# Light_Shield_Test.net
KiCad netlist of a schematic drawn in EAGLE
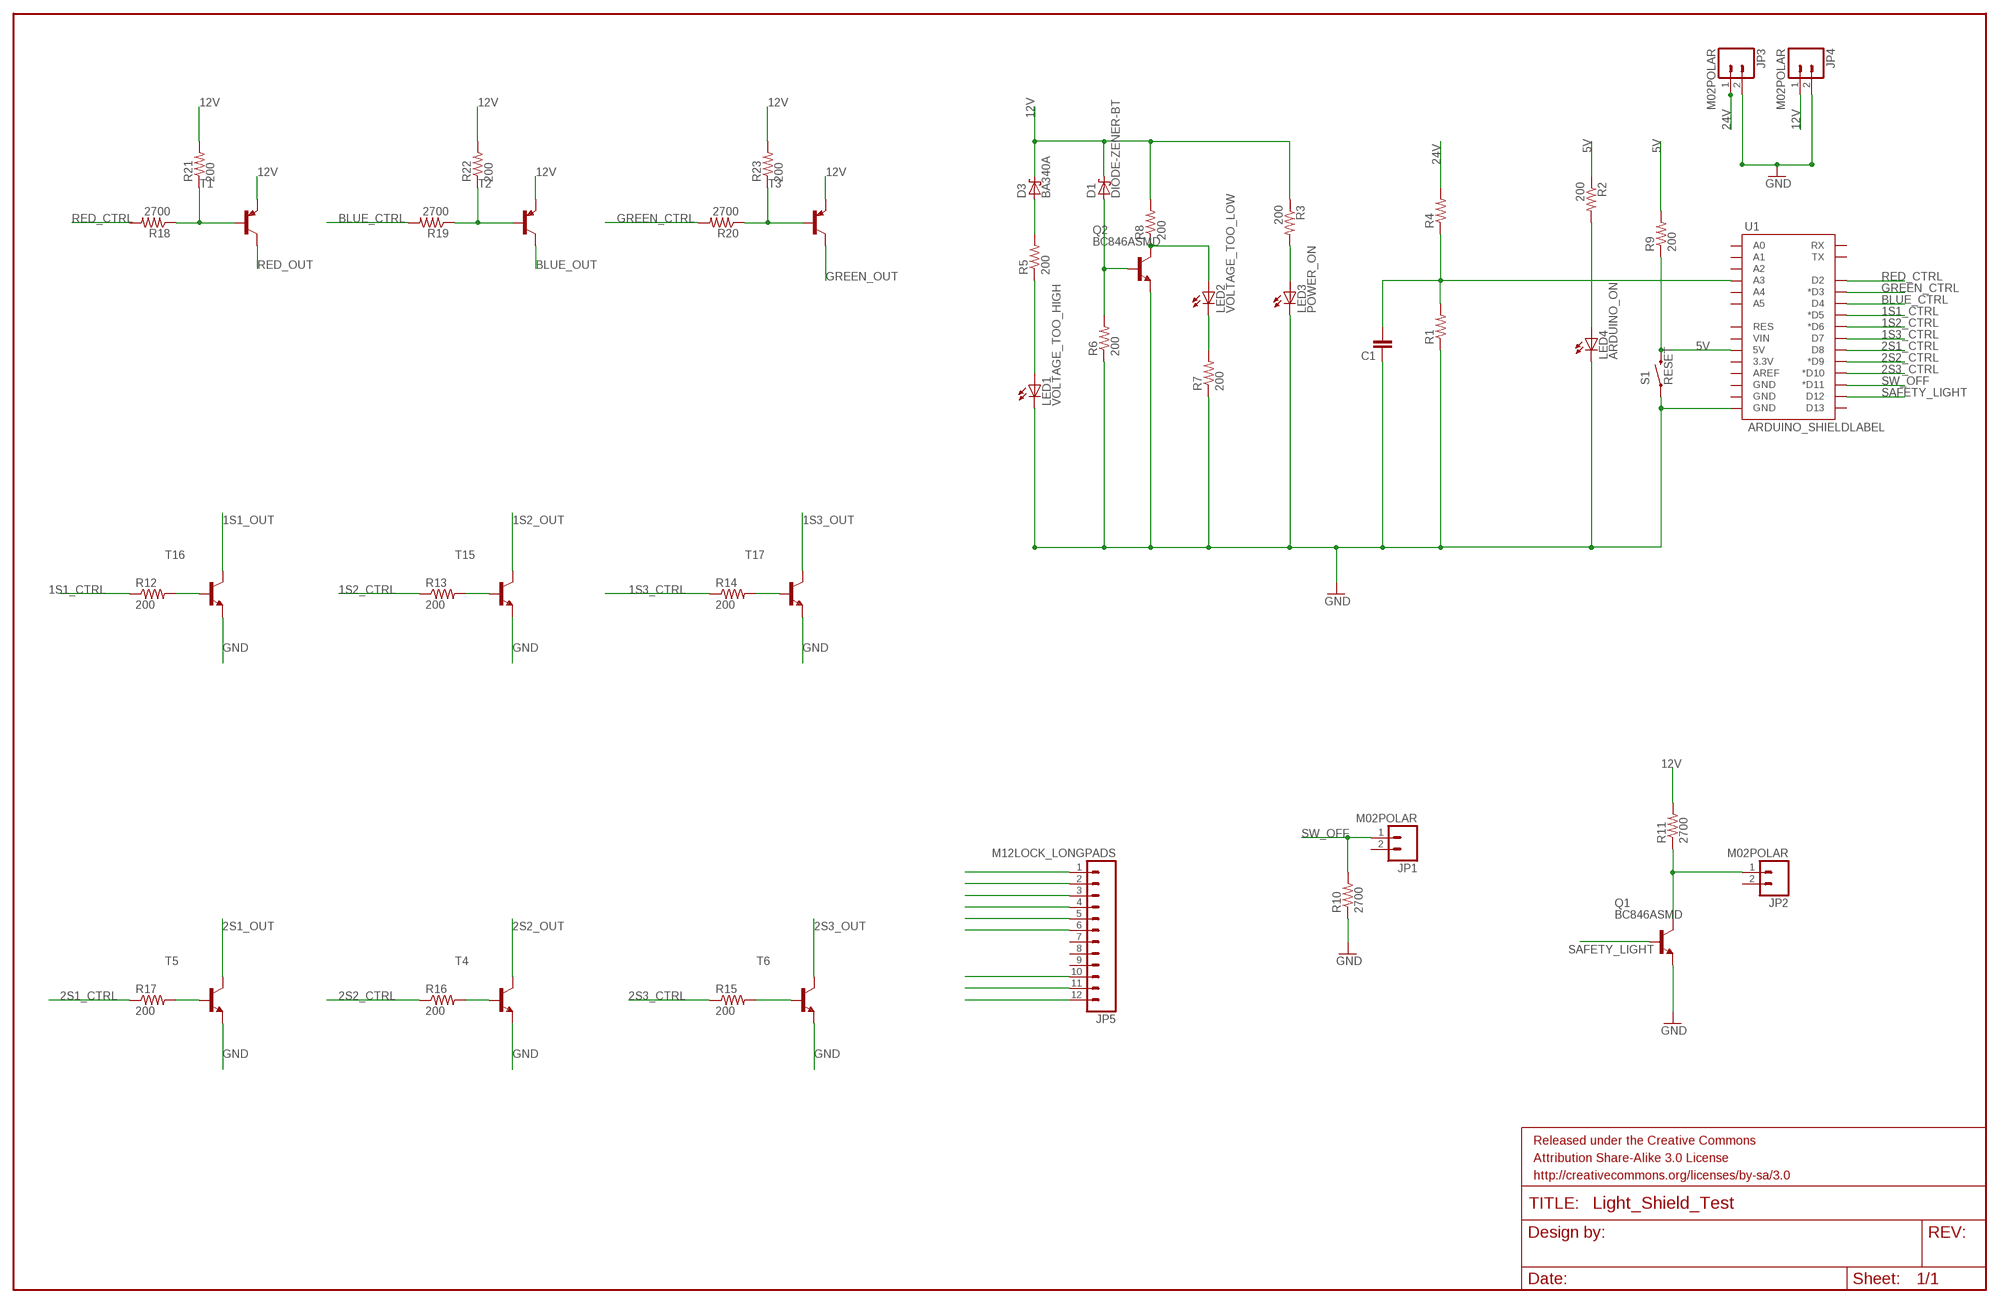
[diagram p0: schematic, sheet 1]

(export (version "E")
  (design (tool "Eeschema 10.0.6"))
  (components
    (comp (ref "C1")
      (value "CAP0402-CAP")
      (footprint "eagle-import:0402-CAP")
      (libsource (lib "eagle-import") (part "CAP0402-CAP"))
    )
    (comp (ref "D1")
      (value "DIODE-ZENER-BT")
      (footprint "eagle-import:SOD123FL")
      (libsource (lib "eagle-import") (part "SMF5.0AT1"))
    )
    (comp (ref "D3")
      (value "BA340A")
      (footprint "eagle-import:SOD123FL")
      (libsource (lib "eagle-import") (part "SMF5.0AT1"))
    )
    (comp (ref "FRAME1")
      (value "FRAME-LEDGER")
      (footprint "eagle-import:CREATIVE_COMMONS")
      (libsource (lib "eagle-import") (part "FRAME-LEDGER"))
    )
    (comp (ref "JP1")
      (value "M02POLAR")
      (footprint "eagle-import:MOLEX-1X2")
      (libsource (lib "eagle-import") (part "M02POLAR"))
    )
    (comp (ref "JP2")
      (value "M02POLAR")
      (footprint "eagle-import:MOLEX-1X2")
      (libsource (lib "eagle-import") (part "M02POLAR"))
    )
    (comp (ref "JP3")
      (value "M02POLAR")
      (footprint "eagle-import:MOLEX-1X2")
      (libsource (lib "eagle-import") (part "M02POLAR"))
    )
    (comp (ref "JP4")
      (value "M02POLAR")
      (footprint "eagle-import:MOLEX-1X2")
      (libsource (lib "eagle-import") (part "M02POLAR"))
    )
    (comp (ref "JP5")
      (value "M12LOCK_LONGPADS")
      (footprint "eagle-import:1X12_LOCK_LONGPADS")
      (libsource (lib "eagle-import") (part "M12LOCK_LONGPADS"))
    )
    (comp (ref "LED1")
      (value "VOLTAGE_TOO_HIGH")
      (footprint "eagle-import:SML0603")
      (libsource (lib "eagle-import") (part "LEDSML0603"))
    )
    (comp (ref "LED2")
      (value "VOLTAGE_TOO_LOW")
      (footprint "eagle-import:SML0603")
      (libsource (lib "eagle-import") (part "LEDSML0603"))
    )
    (comp (ref "LED3")
      (value "POWER_ON")
      (footprint "eagle-import:SML0603")
      (libsource (lib "eagle-import") (part "LEDSML0603"))
    )
    (comp (ref "LED4")
      (value "ARDUINO_ON")
      (footprint "eagle-import:SML0603")
      (libsource (lib "eagle-import") (part "LEDSML0603"))
    )
    (comp (ref "Q1")
      (value "BC846ASMD")
      (footprint "eagle-import:SOT23")
      (libsource (lib "eagle-import") (part "BC846SMDA"))
    )
    (comp (ref "Q2")
      (value "BC846ASMD")
      (footprint "eagle-import:SOT23")
      (libsource (lib "eagle-import") (part "BC846SMDA"))
    )
    (comp (ref "R1")
      (value "RESISTOR0402-RES")
      (footprint "eagle-import:0402-RES")
      (libsource (lib "eagle-import") (part "RESISTOR0402-RES"))
    )
    (comp (ref "R2")
      (value "200")
      (footprint "eagle-import:0603-RES")
      (libsource (lib "eagle-import") (part "RESISTOR0603"))
    )
    (comp (ref "R3")
      (value "200")
      (footprint "eagle-import:0603-RES")
      (libsource (lib "eagle-import") (part "RESISTOR0603"))
    )
    (comp (ref "R4")
      (value "RESISTOR0603")
      (footprint "eagle-import:0603-RES")
      (libsource (lib "eagle-import") (part "RESISTOR0603"))
    )
    (comp (ref "R5")
      (value "200")
      (footprint "eagle-import:0603-RES")
      (libsource (lib "eagle-import") (part "RESISTOR0603"))
    )
    (comp (ref "R6")
      (value "200")
      (footprint "eagle-import:0603-RES")
      (libsource (lib "eagle-import") (part "RESISTOR0603"))
    )
    (comp (ref "R7")
      (value "200")
      (footprint "eagle-import:0603-RES")
      (libsource (lib "eagle-import") (part "SparkFun-Resistors_RESISTOR0603-RES"))
    )
    (comp (ref "R8")
      (value "200")
      (footprint "eagle-import:0603-RES")
      (libsource (lib "eagle-import") (part "SparkFun-Resistors_RESISTOR0603-RES"))
    )
    (comp (ref "R9")
      (value "200")
      (footprint "eagle-import:0603-RES")
      (libsource (lib "eagle-import") (part "RESISTOR0603"))
    )
    (comp (ref "R10")
      (value "2700")
      (footprint "eagle-import:0603-RES")
      (libsource (lib "eagle-import") (part "RESISTOR0603"))
    )
    (comp (ref "R11")
      (value "2700")
      (footprint "eagle-import:0603-RES")
      (libsource (lib "eagle-import") (part "RESISTOR0603"))
    )
    (comp (ref "R12")
      (value "200")
      (footprint "eagle-import:0603-RES")
      (libsource (lib "eagle-import") (part "RESISTOR0603"))
    )
    (comp (ref "R13")
      (value "200")
      (footprint "eagle-import:0603-RES")
      (libsource (lib "eagle-import") (part "RESISTOR0603"))
    )
    (comp (ref "R14")
      (value "200")
      (footprint "eagle-import:0603-RES")
      (libsource (lib "eagle-import") (part "RESISTOR0603"))
    )
    (comp (ref "R15")
      (value "200")
      (footprint "eagle-import:0603-RES")
      (libsource (lib "eagle-import") (part "RESISTOR0603"))
    )
    (comp (ref "R16")
      (value "200")
      (footprint "eagle-import:0603-RES")
      (libsource (lib "eagle-import") (part "RESISTOR0603"))
    )
    (comp (ref "R17")
      (value "200")
      (footprint "eagle-import:0603-RES")
      (libsource (lib "eagle-import") (part "RESISTOR0603"))
    )
    (comp (ref "R18")
      (value "2700")
      (footprint "eagle-import:0603-RES")
      (libsource (lib "eagle-import") (part "RESISTOR0603"))
    )
    (comp (ref "R19")
      (value "2700")
      (footprint "eagle-import:0603-RES")
      (libsource (lib "eagle-import") (part "RESISTOR0603"))
    )
    (comp (ref "R20")
      (value "2700")
      (footprint "eagle-import:0603-RES")
      (libsource (lib "eagle-import") (part "RESISTOR0603"))
    )
    (comp (ref "R21")
      (value "200")
      (footprint "eagle-import:0603-RES")
      (libsource (lib "eagle-import") (part "RESISTOR0603"))
    )
    (comp (ref "R22")
      (value "200")
      (footprint "eagle-import:0603-RES")
      (libsource (lib "eagle-import") (part "RESISTOR0603"))
    )
    (comp (ref "R23")
      (value "200")
      (footprint "eagle-import:0603-RES")
      (libsource (lib "eagle-import") (part "RESISTOR0603"))
    )
    (comp (ref "S1")
      (value "RESET")
      (footprint "eagle-import:TACTILE-PTH")
      (libsource (lib "eagle-import") (part "SWITCH-MOMENTARY-2PTH"))
    )
    (comp (ref "T1")
      (value "-PNP-TO220V")
      (footprint "eagle-import:TO220V")
      (libsource (lib "eagle-import") (part "-PNP-TO220V"))
    )
    (comp (ref "T2")
      (value "-PNP-TO220V")
      (footprint "eagle-import:TO220V")
      (libsource (lib "eagle-import") (part "-PNP-TO220V"))
    )
    (comp (ref "T3")
      (value "-PNP-TO220V")
      (footprint "eagle-import:TO220V")
      (libsource (lib "eagle-import") (part "-PNP-TO220V"))
    )
    (comp (ref "T4")
      (value "-NPN-TO220V")
      (footprint "eagle-import:TO220V")
      (libsource (lib "eagle-import") (part "-NPN-TO220V"))
    )
    (comp (ref "T5")
      (value "-NPN-TO220V")
      (footprint "eagle-import:TO220V")
      (libsource (lib "eagle-import") (part "-NPN-TO220V"))
    )
    (comp (ref "T6")
      (value "-NPN-TO220V")
      (footprint "eagle-import:TO220V")
      (libsource (lib "eagle-import") (part "-NPN-TO220V"))
    )
    (comp (ref "T15")
      (value "-NPN-TO220V")
      (footprint "eagle-import:TO220V")
      (libsource (lib "eagle-import") (part "-NPN-TO220V"))
    )
    (comp (ref "T16")
      (value "-NPN-TO220V")
      (footprint "eagle-import:TO220V")
      (libsource (lib "eagle-import") (part "-NPN-TO220V"))
    )
    (comp (ref "T17")
      (value "-NPN-TO220V")
      (footprint "eagle-import:TO220V")
      (libsource (lib "eagle-import") (part "-NPN-TO220V"))
    )
    (comp (ref "U1")
      (value "ARDUINO_SHIELDLABEL")
      (footprint "eagle-import:DUEMILANOVE_SHIELD")
      (libsource (lib "eagle-import") (part "ARDUINO_SHIELDLABEL"))
    )
  )
  (nets
    (net (code "1") (name "/1S1_CTRL") (class "Default")
      (node (ref "R12") (pin "1") (pinfunction "1_1") (pintype "passive"))
      (node (ref "U1") (pin "D5") (pinfunction "*D5_D5") (pintype "bidirectional"))
    )
    (net (code "2") (name "/1S1_OUT") (class "Default")
      (node (ref "JP5") (pin "4") (pinfunction "4_4") (pintype "passive"))
      (node (ref "T16") (pin "2") (pinfunction "C_2") (pintype "passive"))
    )
    (net (code "3") (name "/1S2_CTRL") (class "Default")
      (node (ref "R13") (pin "1") (pinfunction "1_1") (pintype "passive"))
      (node (ref "U1") (pin "D6") (pinfunction "*D6_D6") (pintype "bidirectional"))
    )
    (net (code "4") (name "/1S2_OUT") (class "Default")
      (node (ref "JP5") (pin "5") (pinfunction "5_5") (pintype "passive"))
      (node (ref "T15") (pin "2") (pinfunction "C_2") (pintype "passive"))
    )
    (net (code "5") (name "/1S3_CTRL") (class "Default")
      (node (ref "R14") (pin "1") (pinfunction "1_1") (pintype "passive"))
      (node (ref "U1") (pin "D7") (pinfunction "D7_D7") (pintype "bidirectional"))
    )
    (net (code "6") (name "/1S3_OUT") (class "Default")
      (node (ref "JP5") (pin "6") (pinfunction "6_6") (pintype "passive"))
      (node (ref "T17") (pin "2") (pinfunction "C_2") (pintype "passive"))
    )
    (net (code "7") (name "/2S1_CTRL") (class "Default")
      (node (ref "R17") (pin "1") (pinfunction "1_1") (pintype "passive"))
      (node (ref "U1") (pin "D8") (pinfunction "D8_D8") (pintype "bidirectional"))
    )
    (net (code "8") (name "/2S1_OUT") (class "Default")
      (node (ref "JP5") (pin "10") (pinfunction "10_10") (pintype "passive"))
      (node (ref "T5") (pin "2") (pinfunction "C_2") (pintype "passive"))
    )
    (net (code "9") (name "/2S2_CTRL") (class "Default")
      (node (ref "R16") (pin "1") (pinfunction "1_1") (pintype "passive"))
      (node (ref "U1") (pin "D9") (pinfunction "*D9_D9") (pintype "bidirectional"))
    )
    (net (code "10") (name "/2S2_OUT") (class "Default")
      (node (ref "JP5") (pin "11") (pinfunction "11_11") (pintype "passive"))
      (node (ref "T4") (pin "2") (pinfunction "C_2") (pintype "passive"))
    )
    (net (code "11") (name "/2S3_CTRL") (class "Default")
      (node (ref "R15") (pin "1") (pinfunction "1_1") (pintype "passive"))
      (node (ref "U1") (pin "D10") (pinfunction "*D10_D10") (pintype "bidirectional"))
    )
    (net (code "12") (name "/2S3_OUT") (class "Default")
      (node (ref "JP5") (pin "12") (pinfunction "12_12") (pintype "passive"))
      (node (ref "T6") (pin "2") (pinfunction "C_2") (pintype "passive"))
    )
    (net (code "13") (name "/5V") (class "Default")
      (node (ref "R2") (pin "1") (pinfunction "1_1") (pintype "passive"))
      (node (ref "R9") (pin "1") (pinfunction "1_1") (pintype "passive"))
      (node (ref "R9") (pin "2") (pinfunction "2_2") (pintype "passive"))
      (node (ref "S1") (pin "3") (pinfunction "2_3") (pintype "passive"))
      (node (ref "U1") (pin "5V") (pinfunction "5V_5V") (pintype "bidirectional"))
    )
    (net (code "14") (name "/12V") (class "Default")
      (node (ref "D1") (pin "C") (pinfunction "C_C") (pintype "passive"))
      (node (ref "D3") (pin "C") (pinfunction "C_C") (pintype "passive"))
      (node (ref "JP4") (pin "1") (pinfunction "1_1") (pintype "passive"))
      (node (ref "R11") (pin "2") (pinfunction "2_2") (pintype "passive"))
      (node (ref "R21") (pin "2") (pinfunction "2_2") (pintype "passive"))
      (node (ref "R22") (pin "2") (pinfunction "2_2") (pintype "passive"))
      (node (ref "R23") (pin "2") (pinfunction "2_2") (pintype "passive"))
      (node (ref "R3") (pin "1") (pinfunction "1_1") (pintype "passive"))
      (node (ref "R8") (pin "2") (pinfunction "2_2") (pintype "passive"))
      (node (ref "T1") (pin "3") (pinfunction "E_3") (pintype "passive"))
      (node (ref "T2") (pin "3") (pinfunction "E_3") (pintype "passive"))
      (node (ref "T3") (pin "3") (pinfunction "E_3") (pintype "passive"))
    )
    (net (code "15") (name "/24V") (class "Default")
      (node (ref "JP3") (pin "1") (pinfunction "1_1") (pintype "passive"))
      (node (ref "R4") (pin "2") (pinfunction "2_2") (pintype "passive"))
    )
    (net (code "16") (name "/BLUE_CTRL") (class "Default")
      (node (ref "R19") (pin "2") (pinfunction "2_2") (pintype "passive"))
      (node (ref "U1") (pin "D4") (pinfunction "D4_D4") (pintype "bidirectional"))
    )
    (net (code "17") (name "/BLUE_OUT") (class "Default")
      (node (ref "JP5") (pin "1") (pinfunction "1_1") (pintype "passive"))
      (node (ref "T2") (pin "2") (pinfunction "C_2") (pintype "passive"))
    )
    (net (code "18") (name "/GREEN_CTRL") (class "Default")
      (node (ref "R20") (pin "2") (pinfunction "2_2") (pintype "passive"))
      (node (ref "U1") (pin "D3") (pinfunction "*D3_D3") (pintype "bidirectional"))
    )
    (net (code "19") (name "/GREEN_OUT") (class "Default")
      (node (ref "JP5") (pin "2") (pinfunction "2_2") (pintype "passive"))
      (node (ref "T3") (pin "2") (pinfunction "C_2") (pintype "passive"))
    )
    (net (code "20") (name "/RED_CTRL") (class "Default")
      (node (ref "R18") (pin "2") (pinfunction "2_2") (pintype "passive"))
      (node (ref "U1") (pin "D2") (pinfunction "D2_D2") (pintype "bidirectional"))
    )
    (net (code "21") (name "/RED_OUT") (class "Default")
      (node (ref "JP5") (pin "3") (pinfunction "3_3") (pintype "passive"))
      (node (ref "T1") (pin "2") (pinfunction "C_2") (pintype "passive"))
    )
    (net (code "22") (name "/SAFETY_LIGHT") (class "Default")
      (node (ref "Q1") (pin "1") (pinfunction "B_1") (pintype "passive"))
      (node (ref "U1") (pin "D12") (pinfunction "D12_D12") (pintype "bidirectional"))
    )
    (net (code "23") (name "/SW_OFF") (class "Default")
      (node (ref "JP1") (pin "1") (pinfunction "1_1") (pintype "passive"))
      (node (ref "R10") (pin "2") (pinfunction "2_2") (pintype "passive"))
      (node (ref "U1") (pin "D11") (pinfunction "*D11_D11") (pintype "bidirectional"))
    )
    (net (code "24") (name "GND") (class "Default")
      (node (ref "C1") (pin "1") (pinfunction "1_1") (pintype "passive"))
      (node (ref "JP3") (pin "2") (pinfunction "2_2") (pintype "passive"))
      (node (ref "JP4") (pin "2") (pinfunction "2_2") (pintype "passive"))
      (node (ref "LED1") (pin "C") (pinfunction "C_C") (pintype "passive"))
      (node (ref "LED3") (pin "C") (pinfunction "C_C") (pintype "passive"))
      (node (ref "LED4") (pin "C") (pinfunction "C_C") (pintype "passive"))
      (node (ref "Q1") (pin "2") (pinfunction "E_2") (pintype "passive"))
      (node (ref "Q2") (pin "2") (pinfunction "E_2") (pintype "passive"))
      (node (ref "R1") (pin "1") (pinfunction "1_1") (pintype "passive"))
      (node (ref "R10") (pin "1") (pinfunction "1_1") (pintype "passive"))
      (node (ref "R6") (pin "1") (pinfunction "1_1") (pintype "passive"))
      (node (ref "R7") (pin "1") (pinfunction "1_1") (pintype "passive"))
      (node (ref "S1") (pin "1") (pinfunction "1_1") (pintype "passive"))
      (node (ref "T15") (pin "3") (pinfunction "E_3") (pintype "passive"))
      (node (ref "T16") (pin "3") (pinfunction "E_3") (pintype "passive"))
      (node (ref "T17") (pin "3") (pinfunction "E_3") (pintype "passive"))
      (node (ref "T4") (pin "3") (pinfunction "E_3") (pintype "passive"))
      (node (ref "T5") (pin "3") (pinfunction "E_3") (pintype "passive"))
      (node (ref "T6") (pin "3") (pinfunction "E_3") (pintype "passive"))
      (node (ref "U1") (pin "GND@0") (pinfunction "GND_GND@0") (pintype "bidirectional"))
    )
    (net (code "25") (name "Net-(C1-Pad2)") (class "Default")
      (node (ref "C1") (pin "2") (pinfunction "2_2") (pintype "passive"))
      (node (ref "R1") (pin "2") (pinfunction "2_2") (pintype "passive"))
      (node (ref "R4") (pin "1") (pinfunction "1_1") (pintype "passive"))
      (node (ref "U1") (pin "A3") (pinfunction "A3_A3") (pintype "bidirectional"))
    )
    (net (code "26") (name "Net-(D3-PadA)") (class "Default")
      (node (ref "D3") (pin "A") (pinfunction "A_A") (pintype "passive"))
      (node (ref "R5") (pin "2") (pinfunction "2_2") (pintype "passive"))
    )
    (net (code "27") (name "Net-(LED1-PadA)") (class "Default")
      (node (ref "LED1") (pin "A") (pinfunction "A_A") (pintype "passive"))
      (node (ref "R5") (pin "1") (pinfunction "1_1") (pintype "passive"))
    )
    (net (code "28") (name "Net-(LED2-PadC)") (class "Default")
      (node (ref "LED2") (pin "C") (pinfunction "C_C") (pintype "passive"))
      (node (ref "R7") (pin "2") (pinfunction "2_2") (pintype "passive"))
    )
    (net (code "29") (name "Net-(LED3-PadA)") (class "Default")
      (node (ref "LED3") (pin "A") (pinfunction "A_A") (pintype "passive"))
      (node (ref "R3") (pin "2") (pinfunction "2_2") (pintype "passive"))
    )
    (net (code "30") (name "Net-(LED4-PadA)") (class "Default")
      (node (ref "LED4") (pin "A") (pinfunction "A_A") (pintype "passive"))
      (node (ref "R2") (pin "2") (pinfunction "2_2") (pintype "passive"))
    )
    (net (code "31") (name "Net-(Q1-C)") (class "Default")
      (node (ref "JP2") (pin "1") (pinfunction "1_1") (pintype "passive"))
      (node (ref "Q1") (pin "3") (pinfunction "C_3") (pintype "passive"))
      (node (ref "R11") (pin "1") (pinfunction "1_1") (pintype "passive"))
    )
    (net (code "32") (name "Net-(Q2-B)") (class "Default")
      (node (ref "D1") (pin "A") (pinfunction "A_A") (pintype "passive"))
      (node (ref "Q2") (pin "1") (pinfunction "B_1") (pintype "passive"))
      (node (ref "R6") (pin "2") (pinfunction "2_2") (pintype "passive"))
    )
    (net (code "33") (name "Net-(Q2-C)") (class "Default")
      (node (ref "LED2") (pin "A") (pinfunction "A_A") (pintype "passive"))
      (node (ref "Q2") (pin "3") (pinfunction "C_3") (pintype "passive"))
      (node (ref "R8") (pin "1") (pinfunction "1_1") (pintype "passive"))
    )
    (net (code "34") (name "Net-(T1-B)") (class "Default")
      (node (ref "R18") (pin "1") (pinfunction "1_1") (pintype "passive"))
      (node (ref "R21") (pin "1") (pinfunction "1_1") (pintype "passive"))
      (node (ref "T1") (pin "1") (pinfunction "B_1") (pintype "passive"))
    )
    (net (code "35") (name "Net-(T2-B)") (class "Default")
      (node (ref "R19") (pin "1") (pinfunction "1_1") (pintype "passive"))
      (node (ref "R22") (pin "1") (pinfunction "1_1") (pintype "passive"))
      (node (ref "T2") (pin "1") (pinfunction "B_1") (pintype "passive"))
    )
    (net (code "36") (name "Net-(T3-B)") (class "Default")
      (node (ref "R20") (pin "1") (pinfunction "1_1") (pintype "passive"))
      (node (ref "R23") (pin "1") (pinfunction "1_1") (pintype "passive"))
      (node (ref "T3") (pin "1") (pinfunction "B_1") (pintype "passive"))
    )
    (net (code "37") (name "Net-(T4-B)") (class "Default")
      (node (ref "R16") (pin "2") (pinfunction "2_2") (pintype "passive"))
      (node (ref "T4") (pin "1") (pinfunction "B_1") (pintype "passive"))
    )
    (net (code "38") (name "Net-(T5-B)") (class "Default")
      (node (ref "R17") (pin "2") (pinfunction "2_2") (pintype "passive"))
      (node (ref "T5") (pin "1") (pinfunction "B_1") (pintype "passive"))
    )
    (net (code "39") (name "Net-(T6-B)") (class "Default")
      (node (ref "R15") (pin "2") (pinfunction "2_2") (pintype "passive"))
      (node (ref "T6") (pin "1") (pinfunction "B_1") (pintype "passive"))
    )
    (net (code "40") (name "Net-(T15-B)") (class "Default")
      (node (ref "R13") (pin "2") (pinfunction "2_2") (pintype "passive"))
      (node (ref "T15") (pin "1") (pinfunction "B_1") (pintype "passive"))
    )
    (net (code "41") (name "Net-(T16-B)") (class "Default")
      (node (ref "R12") (pin "2") (pinfunction "2_2") (pintype "passive"))
      (node (ref "T16") (pin "1") (pinfunction "B_1") (pintype "passive"))
    )
    (net (code "42") (name "Net-(T17-B)") (class "Default")
      (node (ref "R14") (pin "2") (pinfunction "2_2") (pintype "passive"))
      (node (ref "T17") (pin "1") (pinfunction "B_1") (pintype "passive"))
    )
    (net (code "43") (name "unconnected-(JP1-Pad2)") (class "Default")
      (node (ref "JP1") (pin "2") (pinfunction "2_2") (pintype "passive"))
    )
    (net (code "44") (name "unconnected-(JP2-Pad2)") (class "Default")
      (node (ref "JP2") (pin "2") (pinfunction "2_2") (pintype "passive"))
    )
    (net (code "45") (name "unconnected-(JP5-Pad7)") (class "Default")
      (node (ref "JP5") (pin "7") (pinfunction "7_7") (pintype "passive"))
    )
    (net (code "46") (name "unconnected-(JP5-Pad8)") (class "Default")
      (node (ref "JP5") (pin "8") (pinfunction "8_8") (pintype "passive"))
    )
    (net (code "47") (name "unconnected-(JP5-Pad9)") (class "Default")
      (node (ref "JP5") (pin "9") (pinfunction "9_9") (pintype "passive"))
    )
    (net (code "48") (name "unconnected-(U1-GND-PadGND@1)") (class "Default")
      (node (ref "U1") (pin "GND@1") (pinfunction "GND_GND@1") (pintype "bidirectional"))
    )
    (net (code "49") (name "unconnected-(U1-GND-PadGND@2)") (class "Default")
      (node (ref "U1") (pin "GND@2") (pinfunction "GND_GND@2") (pintype "bidirectional"))
    )
    (net (code "50") (name "unconnected-(U1-Pad3.3V)") (class "Default")
      (node (ref "U1") (pin "3.3V") (pinfunction "3.3V_3.3V") (pintype "bidirectional"))
    )
    (net (code "51") (name "unconnected-(U1-PadA0)") (class "Default")
      (node (ref "U1") (pin "A0") (pinfunction "A0_A0") (pintype "bidirectional"))
    )
    (net (code "52") (name "unconnected-(U1-PadA1)") (class "Default")
      (node (ref "U1") (pin "A1") (pinfunction "A1_A1") (pintype "bidirectional"))
    )
    (net (code "53") (name "unconnected-(U1-PadA2)") (class "Default")
      (node (ref "U1") (pin "A2") (pinfunction "A2_A2") (pintype "bidirectional"))
    )
    (net (code "54") (name "unconnected-(U1-PadA4)") (class "Default")
      (node (ref "U1") (pin "A4") (pinfunction "A4_A4") (pintype "bidirectional"))
    )
    (net (code "55") (name "unconnected-(U1-PadA5)") (class "Default")
      (node (ref "U1") (pin "A5") (pinfunction "A5_A5") (pintype "bidirectional"))
    )
    (net (code "56") (name "unconnected-(U1-PadAREF)") (class "Default")
      (node (ref "U1") (pin "AREF") (pinfunction "AREF_AREF") (pintype "bidirectional"))
    )
    (net (code "57") (name "unconnected-(U1-PadD13)") (class "Default")
      (node (ref "U1") (pin "D13") (pinfunction "D13_D13") (pintype "bidirectional"))
    )
    (net (code "58") (name "unconnected-(U1-PadRES)") (class "Default")
      (node (ref "U1") (pin "RES") (pinfunction "RES_RES") (pintype "bidirectional"))
    )
    (net (code "59") (name "unconnected-(U1-PadRX)") (class "Default")
      (node (ref "U1") (pin "RX") (pinfunction "RX_RX") (pintype "bidirectional"))
    )
    (net (code "60") (name "unconnected-(U1-PadTX)") (class "Default")
      (node (ref "U1") (pin "TX") (pinfunction "TX_TX") (pintype "bidirectional"))
    )
    (net (code "61") (name "unconnected-(U1-PadVIN)") (class "Default")
      (node (ref "U1") (pin "VIN") (pinfunction "VIN_VIN") (pintype "bidirectional"))
    )
  )
)
